# ghc-silk.net
KiCad netlist of a schematic drawn in EAGLE
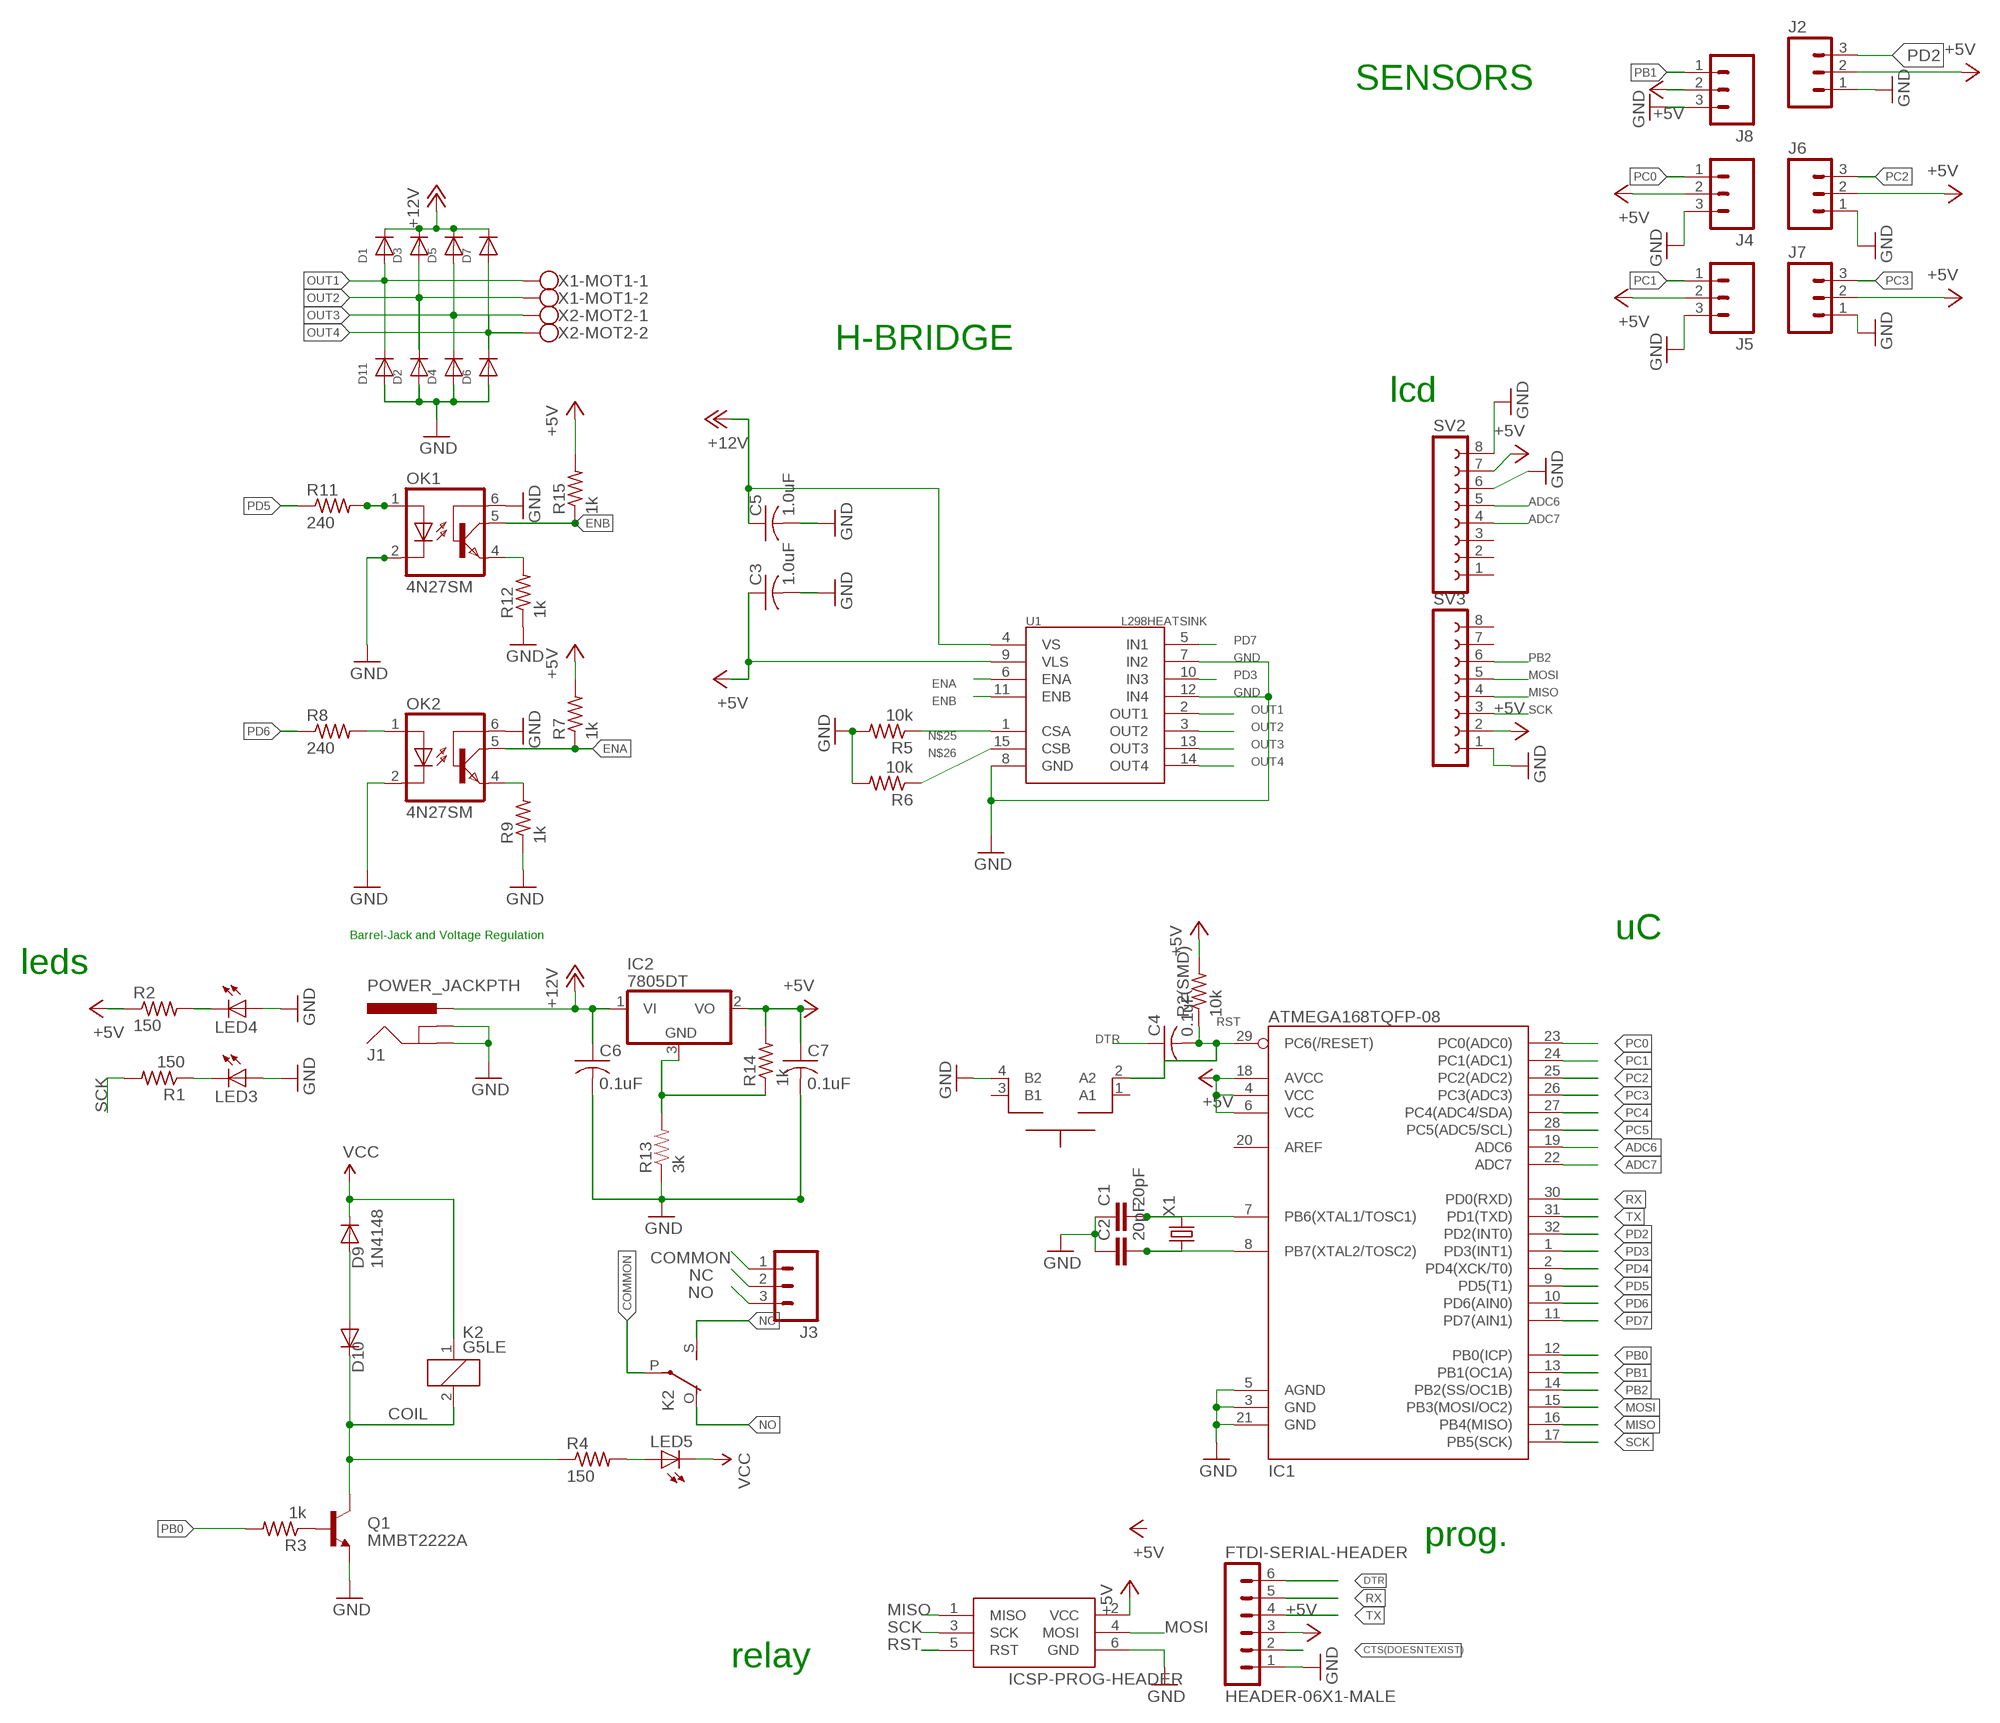
[diagram p0: schematic, sheet 1]

(export (version "E")
  (design (tool "Eeschema 10.0.6"))
  (components
    (comp (ref "C1")
      (value "20pF")
      (footprint "eagle-import:C0805")
      (libsource (lib "eagle-import") (part "C-EUC0805"))
    )
    (comp (ref "C2")
      (value "20pF")
      (footprint "eagle-import:C0805")
      (libsource (lib "eagle-import") (part "C-EUC0805"))
    )
    (comp (ref "C3")
      (value "1.0uF")
      (footprint "eagle-import:C0805")
      (libsource (lib "eagle-import") (part "C-USC0805"))
    )
    (comp (ref "C4")
      (value "0.1uF")
      (footprint "eagle-import:C0805")
      (libsource (lib "eagle-import") (part "C-USC0805"))
    )
    (comp (ref "C5")
      (value "1.0uF")
      (footprint "eagle-import:C0805")
      (libsource (lib "eagle-import") (part "C-USC0805"))
    )
    (comp (ref "C6")
      (value "0.1uF")
      (footprint "eagle-import:C0805")
      (libsource (lib "eagle-import") (part "C-USC0805"))
    )
    (comp (ref "C7")
      (value "0.1uF")
      (footprint "eagle-import:C0805")
      (libsource (lib "eagle-import") (part "C-USC0805"))
    )
    (comp (ref "D1")
      (value "DIODESOD-523")
      (footprint "eagle-import:SOD-523")
      (libsource (lib "eagle-import") (part "DIODESOD-523"))
    )
    (comp (ref "D2")
      (value "DIODESOD-523")
      (footprint "eagle-import:SOD-523")
      (libsource (lib "eagle-import") (part "DIODESOD-523"))
    )
    (comp (ref "D3")
      (value "DIODESOD-523")
      (footprint "eagle-import:SOD-523")
      (libsource (lib "eagle-import") (part "DIODESOD-523"))
    )
    (comp (ref "D4")
      (value "DIODESOD-523")
      (footprint "eagle-import:SOD-523")
      (libsource (lib "eagle-import") (part "DIODESOD-523"))
    )
    (comp (ref "D5")
      (value "DIODESOD-523")
      (footprint "eagle-import:SOD-523")
      (libsource (lib "eagle-import") (part "DIODESOD-523"))
    )
    (comp (ref "D6")
      (value "DIODESOD-523")
      (footprint "eagle-import:SOD-523")
      (libsource (lib "eagle-import") (part "DIODESOD-523"))
    )
    (comp (ref "D7")
      (value "DIODESOD-523")
      (footprint "eagle-import:SOD-523")
      (libsource (lib "eagle-import") (part "DIODESOD-523"))
    )
    (comp (ref "D9")
      (value "1N4148")
      (footprint "eagle-import:SOD-323F")
      (libsource (lib "eagle-import") (part "DIODESOD-323F"))
    )
    (comp (ref "D10")
      (value "Zener")
      (footprint "eagle-import:SOD-323F")
      (libsource (lib "eagle-import") (part "DIODESOD-323F"))
    )
    (comp (ref "D11")
      (value "DIODESOD-523")
      (footprint "eagle-import:SOD-523")
      (libsource (lib "eagle-import") (part "DIODESOD-523"))
    )
    (comp (ref "FTDI-SERIAL-HEADER")
      (value "HEADER-06X1-MALE")
      (footprint "eagle-import:06X1-PTH")
      (libsource (lib "eagle-import") (part "HEADER-06X1?-MALE"))
    )
    (comp (ref "IC1")
      (value "ATMEGA168TQFP-08")
      (footprint "eagle-import:TQFP32-08")
      (libsource (lib "eagle-import") (part "ATMEGA168TQFP-08"))
    )
    (comp (ref "IC2")
      (value "7805DT")
      (footprint "eagle-import:TO252")
      (libsource (lib "eagle-import") (part "78DT05"))
    )
    (comp (ref "ICSP-PROG-HEADER")
      (value "AVRISP-6")
      (footprint "eagle-import:AVRISP")
      (libsource (lib "eagle-import") (part "AVRISP-6"))
    )
    (comp (ref "J1")
      (value "POWER_JACKPTH")
      (footprint "eagle-import:POWER_JACK_PTH")
      (libsource (lib "eagle-import") (part "POWER_JACKPTH"))
    )
    (comp (ref "J2")
      (value "M03SCREW_LOCK")
      (footprint "eagle-import:SCREWTERMINAL-3.5MM-3_LOCK.007S")
      (libsource (lib "eagle-import") (part "M03SCREW_LOCK"))
    )
    (comp (ref "J3")
      (value "M03-SCREW-5MM")
      (footprint "eagle-import:SCREWTERMINAL-5MM-3")
      (libsource (lib "eagle-import") (part "M03-SCREW-5MM"))
    )
    (comp (ref "J4")
      (value "M03SCREW_LOCK")
      (footprint "eagle-import:SCREWTERMINAL-3.5MM-3_LOCK.007S")
      (libsource (lib "eagle-import") (part "M03SCREW_LOCK"))
    )
    (comp (ref "J5")
      (value "M03SCREW_LOCK")
      (footprint "eagle-import:SCREWTERMINAL-3.5MM-3_LOCK.007S")
      (libsource (lib "eagle-import") (part "M03SCREW_LOCK"))
    )
    (comp (ref "J6")
      (value "M03SCREW_LOCK")
      (footprint "eagle-import:SCREWTERMINAL-3.5MM-3_LOCK.007S")
      (libsource (lib "eagle-import") (part "M03SCREW_LOCK"))
    )
    (comp (ref "J7")
      (value "M03SCREW_LOCK")
      (footprint "eagle-import:SCREWTERMINAL-3.5MM-3_LOCK.007S")
      (libsource (lib "eagle-import") (part "M03SCREW_LOCK"))
    )
    (comp (ref "J8")
      (value "M03SCREW_LOCK")
      (footprint "eagle-import:SCREWTERMINAL-3.5MM-3_LOCK.007S")
      (libsource (lib "eagle-import") (part "M03SCREW_LOCK"))
    )
    (comp (ref "K2")
      (value "G5LE")
      (footprint "eagle-import:G5LE")
      (libsource (lib "eagle-import") (part "G5LE"))
    )
    (comp (ref "LED3")
      (value "LEDCHIP-LED0805")
      (footprint "eagle-import:CHIP-LED0805")
      (libsource (lib "eagle-import") (part "LEDCHIP-LED0805"))
    )
    (comp (ref "LED4")
      (value "LEDCHIP-LED0805")
      (footprint "eagle-import:CHIP-LED0805")
      (libsource (lib "eagle-import") (part "LEDCHIP-LED0805"))
    )
    (comp (ref "LED5")
      (value "LEDCHIP-LED0805")
      (footprint "eagle-import:CHIP-LED0805")
      (libsource (lib "eagle-import") (part "LEDCHIP-LED0805"))
    )
    (comp (ref "OK1")
      (value "4N27SM")
      (footprint "eagle-import:DIL6-SMD")
      (fields (field (name "MF") "FAIRCHILD SEMICONDUCTOR") (field (name "MPN") "4N27S-M"))
      (libsource (lib "eagle-import") (part "4N?MS27"))
    )
    (comp (ref "OK2")
      (value "4N27SM")
      (footprint "eagle-import:DIL6-SMD")
      (fields (field (name "MF") "FAIRCHILD SEMICONDUCTOR") (field (name "MPN") "4N27S-M"))
      (libsource (lib "eagle-import") (part "4N?MS27"))
    )
    (comp (ref "Q1")
      (value "MMBT2222A")
      (footprint "eagle-import:SOT23-3")
      (libsource (lib "eagle-import") (part "TRANSISTOR_NPNMMBT2222A"))
    )
    (comp (ref "R1")
      (value "150")
      (footprint "eagle-import:M0805")
      (libsource (lib "eagle-import") (part "R-US_M0805"))
    )
    (comp (ref "R2")
      (value "150")
      (footprint "eagle-import:M0805")
      (libsource (lib "eagle-import") (part "R-US_M0805"))
    )
    (comp (ref "R2(SMD)")
      (value "10k")
      (footprint "eagle-import:M0805")
      (libsource (lib "eagle-import") (part "R-US_M0805"))
    )
    (comp (ref "R3")
      (value "1k")
      (footprint "eagle-import:M0805")
      (libsource (lib "eagle-import") (part "R-US_M0805"))
    )
    (comp (ref "R4")
      (value "150")
      (footprint "eagle-import:M0805")
      (libsource (lib "eagle-import") (part "R-US_M0805"))
    )
    (comp (ref "R5")
      (value "10k")
      (footprint "eagle-import:M0805")
      (libsource (lib "eagle-import") (part "R-US_M0805"))
    )
    (comp (ref "R6")
      (value "10k")
      (footprint "eagle-import:M0805")
      (libsource (lib "eagle-import") (part "R-US_M0805"))
    )
    (comp (ref "R7")
      (value "1k")
      (footprint "eagle-import:M0805")
      (libsource (lib "eagle-import") (part "R-US_M0805"))
    )
    (comp (ref "R8")
      (value "240")
      (footprint "eagle-import:M0805")
      (libsource (lib "eagle-import") (part "R-US_M0805"))
    )
    (comp (ref "R9")
      (value "1k")
      (footprint "eagle-import:M0805")
      (libsource (lib "eagle-import") (part "R-US_M0805"))
    )
    (comp (ref "R11")
      (value "240")
      (footprint "eagle-import:M0805")
      (libsource (lib "eagle-import") (part "R-US_M0805"))
    )
    (comp (ref "R12")
      (value "1k")
      (footprint "eagle-import:M0805")
      (libsource (lib "eagle-import") (part "R-US_M0805"))
    )
    (comp (ref "R13")
      (value "3k")
      (footprint "eagle-import:0402-RES")
      (libsource (lib "eagle-import") (part "RESISTOR0402"))
    )
    (comp (ref "R14")
      (value "1k")
      (footprint "eagle-import:M0805")
      (libsource (lib "eagle-import") (part "R-US_M0805"))
    )
    (comp (ref "R15")
      (value "1k")
      (footprint "eagle-import:M0805")
      (libsource (lib "eagle-import") (part "R-US_M0805"))
    )
    (comp (ref "SV2")
      (value "FE08-1")
      (footprint "eagle-import:FE08")
      (libsource (lib "eagle-import") (part "FE08-1"))
    )
    (comp (ref "SV3")
      (value "FE08-1")
      (footprint "eagle-import:FE08")
      (libsource (lib "eagle-import") (part "FE08-1"))
    )
    (comp (ref "SW2")
      (value "MOMENTARYBUTTON")
      (footprint "eagle-import:SPST_NO_SMD")
      (libsource (lib "eagle-import") (part "MOMENTARYBUTTON"))
    )
    (comp (ref "U1")
      (value "L298HEATSINK")
      (footprint "eagle-import:MULTIWATT15_6400BGHEATSINK")
      (libsource (lib "eagle-import") (part "L298HEATSINK"))
    )
    (comp (ref "X1")
      (value "CRYSTALHC49UP")
      (footprint "eagle-import:HC49UP")
      (libsource (lib "eagle-import") (part "CRYSTALHC49UP"))
    )
    (comp (ref "X1-MOT1")
      (value "W237-102")
      (footprint "eagle-import:W237-102")
      (fields (field (name "MPN") "237-102"))
      (libsource (lib "eagle-import") (part "W237-102"))
    )
    (comp (ref "X2-MOT2")
      (value "W237-102")
      (footprint "eagle-import:W237-102")
      (fields (field (name "MPN") "237-102"))
      (libsource (lib "eagle-import") (part "W237-102"))
    )
  )
  (nets
    (net (code "1") (name "+5V") (class "Default")
      (node (ref "C3") (pin "1") (pinfunction "1_1") (pintype "passive"))
      (node (ref "C7") (pin "1") (pinfunction "1_1") (pintype "passive"))
      (node (ref "FTDI-SERIAL-HEADER") (pin "3") (pinfunction "3_3") (pintype "passive"))
      (node (ref "IC1") (pin "18") (pinfunction "AVCC_18") (pintype "bidirectional"))
      (node (ref "IC1") (pin "4") (pinfunction "VCC_4") (pintype "bidirectional"))
      (node (ref "IC1") (pin "6") (pinfunction "VCC_6") (pintype "bidirectional"))
      (node (ref "IC2") (pin "2") (pinfunction "VO_2") (pintype "passive"))
      (node (ref "ICSP-PROG-HEADER") (pin "2") (pinfunction "VCC_2") (pintype "power_in"))
      (node (ref "J2") (pin "2") (pinfunction "2_2") (pintype "passive"))
      (node (ref "J4") (pin "2") (pinfunction "2_2") (pintype "passive"))
      (node (ref "J5") (pin "2") (pinfunction "2_2") (pintype "passive"))
      (node (ref "J6") (pin "2") (pinfunction "2_2") (pintype "passive"))
      (node (ref "J7") (pin "2") (pinfunction "2_2") (pintype "passive"))
      (node (ref "J8") (pin "2") (pinfunction "2_2") (pintype "passive"))
      (node (ref "R14") (pin "2") (pinfunction "2_2") (pintype "passive"))
      (node (ref "R15") (pin "2") (pinfunction "2_2") (pintype "passive"))
      (node (ref "R2") (pin "1") (pinfunction "1_1") (pintype "passive"))
      (node (ref "R2(SMD)") (pin "2") (pinfunction "2_2") (pintype "passive"))
      (node (ref "R7") (pin "2") (pinfunction "2_2") (pintype "passive"))
      (node (ref "SV2") (pin "7") (pinfunction "7_7") (pintype "passive"))
      (node (ref "SV3") (pin "2") (pinfunction "2_2") (pintype "passive"))
      (node (ref "U1") (pin "9") (pinfunction "VLS_9") (pintype "bidirectional"))
    )
    (net (code "2") (name "+12V") (class "Default")
      (node (ref "C5") (pin "1") (pinfunction "1_1") (pintype "passive"))
      (node (ref "C6") (pin "1") (pinfunction "1_1") (pintype "passive"))
      (node (ref "D1") (pin "K") (pinfunction "C_K") (pintype "passive"))
      (node (ref "D3") (pin "K") (pinfunction "C_K") (pintype "passive"))
      (node (ref "D5") (pin "K") (pinfunction "C_K") (pintype "passive"))
      (node (ref "D7") (pin "K") (pinfunction "C_K") (pintype "passive"))
      (node (ref "IC2") (pin "1") (pinfunction "VI_1") (pintype "input"))
      (node (ref "J1") (pin "PWR") (pinfunction "PWR_PWR") (pintype "bidirectional"))
      (node (ref "U1") (pin "4") (pinfunction "VS_4") (pintype "bidirectional"))
    )
    (net (code "3") (name "/COIL") (class "Default")
      (node (ref "D10") (pin "C") (pinfunction "C_C") (pintype "passive"))
      (node (ref "K2") (pin "2") (pinfunction "2_2") (pintype "passive"))
      (node (ref "Q1") (pin "3") (pinfunction "C_3") (pintype "passive"))
      (node (ref "R4") (pin "1") (pinfunction "1_1") (pintype "passive"))
    )
    (net (code "4") (name "/N$25") (class "Default")
      (node (ref "R5") (pin "1") (pinfunction "1_1") (pintype "passive"))
      (node (ref "U1") (pin "1") (pinfunction "CSA_1") (pintype "bidirectional"))
    )
    (net (code "5") (name "/N$26") (class "Default")
      (node (ref "R6") (pin "1") (pinfunction "1_1") (pintype "passive"))
      (node (ref "U1") (pin "15") (pinfunction "CSB_15") (pintype "bidirectional"))
    )
    (net (code "6") (name "/RST") (class "Default")
      (node (ref "C4") (pin "2") (pinfunction "2_2") (pintype "passive"))
      (node (ref "IC1") (pin "29") (pinfunction "PC6(/RESET)_29") (pintype "bidirectional"))
      (node (ref "ICSP-PROG-HEADER") (pin "5") (pinfunction "RST_5") (pintype "output"))
      (node (ref "R2(SMD)") (pin "1") (pinfunction "1_1") (pintype "passive"))
      (node (ref "SW2") (pin "2") (pinfunction "A2_2") (pintype "bidirectional"))
    )
    (net (code "7") (name "ADC6") (class "Default")
      (node (ref "IC1") (pin "19") (pinfunction "ADC6_19") (pintype "bidirectional"))
      (node (ref "SV2") (pin "5") (pinfunction "5_5") (pintype "passive"))
    )
    (net (code "8") (name "ADC7") (class "Default")
      (node (ref "IC1") (pin "22") (pinfunction "ADC7_22") (pintype "bidirectional"))
      (node (ref "SV2") (pin "4") (pinfunction "4_4") (pintype "passive"))
    )
    (net (code "9") (name "COMMON") (class "Default")
      (node (ref "J3") (pin "1") (pinfunction "1_1") (pintype "passive"))
      (node (ref "K2") (pin "P") (pinfunction "P_P") (pintype "passive"))
    )
    (net (code "10") (name "CTS(DOESNTEXIST)") (class "Default")
      (node (ref "FTDI-SERIAL-HEADER") (pin "2") (pinfunction "2_2") (pintype "passive"))
    )
    (net (code "11") (name "DTR") (class "Default")
      (node (ref "C4") (pin "1") (pinfunction "1_1") (pintype "passive"))
      (node (ref "FTDI-SERIAL-HEADER") (pin "6") (pinfunction "6_6") (pintype "passive"))
    )
    (net (code "12") (name "ENA") (class "Default")
      (node (ref "OK2") (pin "5") (pinfunction "COL_5") (pintype "passive"))
      (node (ref "R7") (pin "1") (pinfunction "1_1") (pintype "passive"))
      (node (ref "U1") (pin "6") (pinfunction "ENA_6") (pintype "bidirectional"))
    )
    (net (code "13") (name "ENB") (class "Default")
      (node (ref "OK1") (pin "5") (pinfunction "COL_5") (pintype "passive"))
      (node (ref "R15") (pin "1") (pinfunction "1_1") (pintype "passive"))
      (node (ref "U1") (pin "11") (pinfunction "ENB_11") (pintype "bidirectional"))
    )
    (net (code "14") (name "GND") (class "Default")
      (node (ref "C1") (pin "1") (pinfunction "1_1") (pintype "passive"))
      (node (ref "C2") (pin "1") (pinfunction "1_1") (pintype "passive"))
      (node (ref "C3") (pin "2") (pinfunction "2_2") (pintype "passive"))
      (node (ref "C5") (pin "2") (pinfunction "2_2") (pintype "passive"))
      (node (ref "C6") (pin "2") (pinfunction "2_2") (pintype "passive"))
      (node (ref "C7") (pin "2") (pinfunction "2_2") (pintype "passive"))
      (node (ref "D11") (pin "A") (pinfunction "A_A") (pintype "passive"))
      (node (ref "D2") (pin "A") (pinfunction "A_A") (pintype "passive"))
      (node (ref "D4") (pin "A") (pinfunction "A_A") (pintype "passive"))
      (node (ref "D6") (pin "A") (pinfunction "A_A") (pintype "passive"))
      (node (ref "FTDI-SERIAL-HEADER") (pin "1") (pinfunction "1_1") (pintype "passive"))
      (node (ref "IC1") (pin "21") (pinfunction "GND_21") (pintype "bidirectional"))
      (node (ref "IC1") (pin "3") (pinfunction "GND_3") (pintype "bidirectional"))
      (node (ref "IC1") (pin "5") (pinfunction "AGND_5") (pintype "bidirectional"))
      (node (ref "ICSP-PROG-HEADER") (pin "6") (pinfunction "GND_6") (pintype "power_in"))
      (node (ref "J1") (pin "GND") (pinfunction "GND_GND") (pintype "bidirectional"))
      (node (ref "J1") (pin "GNDBREAK") (pinfunction "GNDBREAK_GNDBREAK") (pintype "bidirectional"))
      (node (ref "J2") (pin "1") (pinfunction "1_1") (pintype "passive"))
      (node (ref "J4") (pin "3") (pinfunction "3_3") (pintype "passive"))
      (node (ref "J5") (pin "3") (pinfunction "3_3") (pintype "passive"))
      (node (ref "J6") (pin "1") (pinfunction "1_1") (pintype "passive"))
      (node (ref "J7") (pin "1") (pinfunction "1_1") (pintype "passive"))
      (node (ref "J8") (pin "3") (pinfunction "3_3") (pintype "passive"))
      (node (ref "LED3") (pin "A") (pinfunction "A_A") (pintype "passive"))
      (node (ref "LED4") (pin "A") (pinfunction "A_A") (pintype "passive"))
      (node (ref "OK1") (pin "2") (pinfunction "C_2") (pintype "passive"))
      (node (ref "OK1") (pin "6") (pinfunction "BAS_6") (pintype "passive"))
      (node (ref "OK2") (pin "2") (pinfunction "C_2") (pintype "passive"))
      (node (ref "OK2") (pin "6") (pinfunction "BAS_6") (pintype "passive"))
      (node (ref "Q1") (pin "2") (pinfunction "E_2") (pintype "passive"))
      (node (ref "R12") (pin "1") (pinfunction "1_1") (pintype "passive"))
      (node (ref "R13") (pin "1") (pinfunction "1_1") (pintype "passive"))
      (node (ref "R5") (pin "2") (pinfunction "2_2") (pintype "passive"))
      (node (ref "R6") (pin "2") (pinfunction "2_2") (pintype "passive"))
      (node (ref "R9") (pin "1") (pinfunction "1_1") (pintype "passive"))
      (node (ref "SV2") (pin "6") (pinfunction "6_6") (pintype "passive"))
      (node (ref "SV2") (pin "8") (pinfunction "8_8") (pintype "passive"))
      (node (ref "SV3") (pin "1") (pinfunction "1_1") (pintype "passive"))
      (node (ref "SW2") (pin "4") (pinfunction "B2_4") (pintype "bidirectional"))
      (node (ref "U1") (pin "12") (pinfunction "IN4_12") (pintype "bidirectional"))
      (node (ref "U1") (pin "7") (pinfunction "IN2_7") (pintype "bidirectional"))
      (node (ref "U1") (pin "8") (pinfunction "GND_8") (pintype "bidirectional"))
    )
    (net (code "15") (name "MISO") (class "Default")
      (node (ref "IC1") (pin "16") (pinfunction "PB4(MISO)_16") (pintype "bidirectional"))
      (node (ref "ICSP-PROG-HEADER") (pin "1") (pinfunction "MISO_1") (pintype "input"))
      (node (ref "SV3") (pin "4") (pinfunction "4_4") (pintype "passive"))
    )
    (net (code "16") (name "MOSI") (class "Default")
      (node (ref "IC1") (pin "15") (pinfunction "PB3(MOSI/OC2)_15") (pintype "bidirectional"))
      (node (ref "ICSP-PROG-HEADER") (pin "4") (pinfunction "MOSI_4") (pintype "output"))
      (node (ref "SV3") (pin "5") (pinfunction "5_5") (pintype "passive"))
    )
    (net (code "17") (name "NC") (class "Default")
      (node (ref "J3") (pin "2") (pinfunction "2_2") (pintype "passive"))
      (node (ref "K2") (pin "S") (pinfunction "S_S") (pintype "passive"))
    )
    (net (code "18") (name "NO") (class "Default")
      (node (ref "J3") (pin "3") (pinfunction "3_3") (pintype "passive"))
      (node (ref "K2") (pin "O") (pinfunction "O_O") (pintype "passive"))
    )
    (net (code "19") (name "Net-(D10-PadA)") (class "Default")
      (node (ref "D10") (pin "A") (pinfunction "A_A") (pintype "passive"))
      (node (ref "D9") (pin "A") (pinfunction "A_A") (pintype "passive"))
    )
    (net (code "20") (name "Net-(IC1-PB6(XTAL1{slash}TOSC1))") (class "Default")
      (node (ref "C1") (pin "2") (pinfunction "2_2") (pintype "passive"))
      (node (ref "IC1") (pin "7") (pinfunction "PB6(XTAL1/TOSC1)_7") (pintype "bidirectional"))
      (node (ref "X1") (pin "2") (pinfunction "2_2") (pintype "passive"))
    )
    (net (code "21") (name "Net-(IC1-PB7(XTAL2{slash}TOSC2))") (class "Default")
      (node (ref "C2") (pin "2") (pinfunction "2_2") (pintype "passive"))
      (node (ref "IC1") (pin "8") (pinfunction "PB7(XTAL2/TOSC2)_8") (pintype "bidirectional"))
      (node (ref "X1") (pin "1") (pinfunction "1_1") (pintype "passive"))
    )
    (net (code "22") (name "Net-(IC2-GND)") (class "Default")
      (node (ref "IC2") (pin "3") (pinfunction "GND_3") (pintype "passive"))
      (node (ref "R13") (pin "2") (pinfunction "2_2") (pintype "passive"))
      (node (ref "R14") (pin "1") (pinfunction "1_1") (pintype "passive"))
    )
    (net (code "23") (name "Net-(LED3-PadC)") (class "Default")
      (node (ref "LED3") (pin "C") (pinfunction "C_C") (pintype "passive"))
      (node (ref "R1") (pin "1") (pinfunction "1_1") (pintype "passive"))
    )
    (net (code "24") (name "Net-(LED4-PadC)") (class "Default")
      (node (ref "LED4") (pin "C") (pinfunction "C_C") (pintype "passive"))
      (node (ref "R2") (pin "2") (pinfunction "2_2") (pintype "passive"))
    )
    (net (code "25") (name "Net-(LED5-PadA)") (class "Default")
      (node (ref "LED5") (pin "A") (pinfunction "A_A") (pintype "passive"))
      (node (ref "R4") (pin "2") (pinfunction "2_2") (pintype "passive"))
    )
    (net (code "26") (name "Net-(OK1-A)") (class "Default")
      (node (ref "OK1") (pin "1") (pinfunction "A_1") (pintype "passive"))
      (node (ref "R11") (pin "2") (pinfunction "2_2") (pintype "passive"))
    )
    (net (code "27") (name "Net-(OK1-EMI)") (class "Default")
      (node (ref "OK1") (pin "4") (pinfunction "EMI_4") (pintype "passive"))
      (node (ref "R12") (pin "2") (pinfunction "2_2") (pintype "passive"))
    )
    (net (code "28") (name "Net-(OK2-A)") (class "Default")
      (node (ref "OK2") (pin "1") (pinfunction "A_1") (pintype "passive"))
      (node (ref "R8") (pin "2") (pinfunction "2_2") (pintype "passive"))
    )
    (net (code "29") (name "Net-(OK2-EMI)") (class "Default")
      (node (ref "OK2") (pin "4") (pinfunction "EMI_4") (pintype "passive"))
      (node (ref "R9") (pin "2") (pinfunction "2_2") (pintype "passive"))
    )
    (net (code "30") (name "Net-(Q1-B)") (class "Default")
      (node (ref "Q1") (pin "1") (pinfunction "B_1") (pintype "passive"))
      (node (ref "R3") (pin "1") (pinfunction "1_1") (pintype "passive"))
    )
    (net (code "31") (name "OUT1") (class "Default")
      (node (ref "D1") (pin "A") (pinfunction "A_A") (pintype "passive"))
      (node (ref "D11") (pin "K") (pinfunction "C_K") (pintype "passive"))
      (node (ref "U1") (pin "2") (pinfunction "OUT1_2") (pintype "bidirectional"))
      (node (ref "X1-MOT1") (pin "1") (pinfunction "KL_1") (pintype "passive"))
    )
    (net (code "32") (name "OUT2") (class "Default")
      (node (ref "D2") (pin "K") (pinfunction "C_K") (pintype "passive"))
      (node (ref "D3") (pin "A") (pinfunction "A_A") (pintype "passive"))
      (node (ref "U1") (pin "3") (pinfunction "OUT2_3") (pintype "bidirectional"))
      (node (ref "X1-MOT1") (pin "2") (pinfunction "KL_2") (pintype "passive"))
    )
    (net (code "33") (name "OUT3") (class "Default")
      (node (ref "D4") (pin "K") (pinfunction "C_K") (pintype "passive"))
      (node (ref "D5") (pin "A") (pinfunction "A_A") (pintype "passive"))
      (node (ref "U1") (pin "13") (pinfunction "OUT3_13") (pintype "bidirectional"))
      (node (ref "X2-MOT2") (pin "1") (pinfunction "KL_1") (pintype "passive"))
    )
    (net (code "34") (name "OUT4") (class "Default")
      (node (ref "D6") (pin "K") (pinfunction "C_K") (pintype "passive"))
      (node (ref "D7") (pin "A") (pinfunction "A_A") (pintype "passive"))
      (node (ref "U1") (pin "14") (pinfunction "OUT4_14") (pintype "bidirectional"))
      (node (ref "X2-MOT2") (pin "2") (pinfunction "KL_2") (pintype "passive"))
    )
    (net (code "35") (name "PB0") (class "Default")
      (node (ref "IC1") (pin "12") (pinfunction "PB0(ICP)_12") (pintype "bidirectional"))
      (node (ref "R3") (pin "2") (pinfunction "2_2") (pintype "passive"))
    )
    (net (code "36") (name "PB1") (class "Default")
      (node (ref "IC1") (pin "13") (pinfunction "PB1(OC1A)_13") (pintype "bidirectional"))
      (node (ref "J8") (pin "1") (pinfunction "1_1") (pintype "passive"))
    )
    (net (code "37") (name "PB2") (class "Default")
      (node (ref "IC1") (pin "14") (pinfunction "PB2(SS/OC1B)_14") (pintype "bidirectional"))
      (node (ref "SV3") (pin "6") (pinfunction "6_6") (pintype "passive"))
    )
    (net (code "38") (name "PC0") (class "Default")
      (node (ref "IC1") (pin "23") (pinfunction "PC0(ADC0)_23") (pintype "bidirectional"))
      (node (ref "J4") (pin "1") (pinfunction "1_1") (pintype "passive"))
    )
    (net (code "39") (name "PC1") (class "Default")
      (node (ref "IC1") (pin "24") (pinfunction "PC1(ADC1)_24") (pintype "bidirectional"))
      (node (ref "J5") (pin "1") (pinfunction "1_1") (pintype "passive"))
    )
    (net (code "40") (name "PC2") (class "Default")
      (node (ref "IC1") (pin "25") (pinfunction "PC2(ADC2)_25") (pintype "bidirectional"))
      (node (ref "J6") (pin "3") (pinfunction "3_3") (pintype "passive"))
    )
    (net (code "41") (name "PC3") (class "Default")
      (node (ref "IC1") (pin "26") (pinfunction "PC3(ADC3)_26") (pintype "bidirectional"))
      (node (ref "J7") (pin "3") (pinfunction "3_3") (pintype "passive"))
    )
    (net (code "42") (name "PC4") (class "Default")
      (node (ref "IC1") (pin "27") (pinfunction "PC4(ADC4/SDA)_27") (pintype "bidirectional"))
    )
    (net (code "43") (name "PC5") (class "Default")
      (node (ref "IC1") (pin "28") (pinfunction "PC5(ADC5/SCL)_28") (pintype "bidirectional"))
    )
    (net (code "44") (name "PD2") (class "Default")
      (node (ref "IC1") (pin "32") (pinfunction "PD2(INT0)_32") (pintype "bidirectional"))
      (node (ref "J2") (pin "3") (pinfunction "3_3") (pintype "passive"))
    )
    (net (code "45") (name "PD3") (class "Default")
      (node (ref "IC1") (pin "1") (pinfunction "PD3(INT1)_1") (pintype "bidirectional"))
      (node (ref "U1") (pin "10") (pinfunction "IN3_10") (pintype "bidirectional"))
    )
    (net (code "46") (name "PD4") (class "Default")
      (node (ref "IC1") (pin "2") (pinfunction "PD4(XCK/T0)_2") (pintype "bidirectional"))
    )
    (net (code "47") (name "PD5") (class "Default")
      (node (ref "IC1") (pin "9") (pinfunction "PD5(T1)_9") (pintype "bidirectional"))
      (node (ref "R11") (pin "1") (pinfunction "1_1") (pintype "passive"))
    )
    (net (code "48") (name "PD6") (class "Default")
      (node (ref "IC1") (pin "10") (pinfunction "PD6(AIN0)_10") (pintype "bidirectional"))
      (node (ref "R8") (pin "1") (pinfunction "1_1") (pintype "passive"))
    )
    (net (code "49") (name "PD7") (class "Default")
      (node (ref "IC1") (pin "11") (pinfunction "PD7(AIN1)_11") (pintype "bidirectional"))
      (node (ref "U1") (pin "5") (pinfunction "IN1_5") (pintype "bidirectional"))
    )
    (net (code "50") (name "RX") (class "Default")
      (node (ref "FTDI-SERIAL-HEADER") (pin "5") (pinfunction "5_5") (pintype "passive"))
      (node (ref "IC1") (pin "30") (pinfunction "PD0(RXD)_30") (pintype "bidirectional"))
    )
    (net (code "51") (name "SCK") (class "Default")
      (node (ref "IC1") (pin "17") (pinfunction "PB5(SCK)_17") (pintype "bidirectional"))
      (node (ref "ICSP-PROG-HEADER") (pin "3") (pinfunction "SCK_3") (pintype "output"))
      (node (ref "R1") (pin "2") (pinfunction "2_2") (pintype "passive"))
      (node (ref "SV3") (pin "3") (pinfunction "3_3") (pintype "passive"))
    )
    (net (code "52") (name "TX") (class "Default")
      (node (ref "FTDI-SERIAL-HEADER") (pin "4") (pinfunction "4_4") (pintype "passive"))
      (node (ref "IC1") (pin "31") (pinfunction "PD1(TXD)_31") (pintype "bidirectional"))
    )
    (net (code "53") (name "VCC") (class "Default")
      (node (ref "D9") (pin "C") (pinfunction "C_C") (pintype "passive"))
      (node (ref "K2") (pin "1") (pinfunction "1_1") (pintype "passive"))
      (node (ref "LED5") (pin "C") (pinfunction "C_C") (pintype "passive"))
    )
    (net (code "54") (name "unconnected-(IC1-AREF-Pad20)") (class "Default")
      (node (ref "IC1") (pin "20") (pinfunction "AREF_20") (pintype "bidirectional"))
    )
    (net (code "55") (name "unconnected-(SV2-Pad1)") (class "Default")
      (node (ref "SV2") (pin "1") (pinfunction "1_1") (pintype "passive"))
    )
    (net (code "56") (name "unconnected-(SV2-Pad2)") (class "Default")
      (node (ref "SV2") (pin "2") (pinfunction "2_2") (pintype "passive"))
    )
    (net (code "57") (name "unconnected-(SV2-Pad3)") (class "Default")
      (node (ref "SV2") (pin "3") (pinfunction "3_3") (pintype "passive"))
    )
    (net (code "58") (name "unconnected-(SV3-Pad7)") (class "Default")
      (node (ref "SV3") (pin "7") (pinfunction "7_7") (pintype "passive"))
    )
    (net (code "59") (name "unconnected-(SV3-Pad8)") (class "Default")
      (node (ref "SV3") (pin "8") (pinfunction "8_8") (pintype "passive"))
    )
    (net (code "60") (name "unconnected-(SW2-A1-Pad1)") (class "Default")
      (node (ref "SW2") (pin "1") (pinfunction "A1_1") (pintype "bidirectional"))
    )
    (net (code "61") (name "unconnected-(SW2-B1-Pad3)") (class "Default")
      (node (ref "SW2") (pin "3") (pinfunction "B1_3") (pintype "bidirectional"))
    )
  )
)
